# Circuito_part1_Altium.net
KiCad netlist of a schematic drawn in Altium Designer
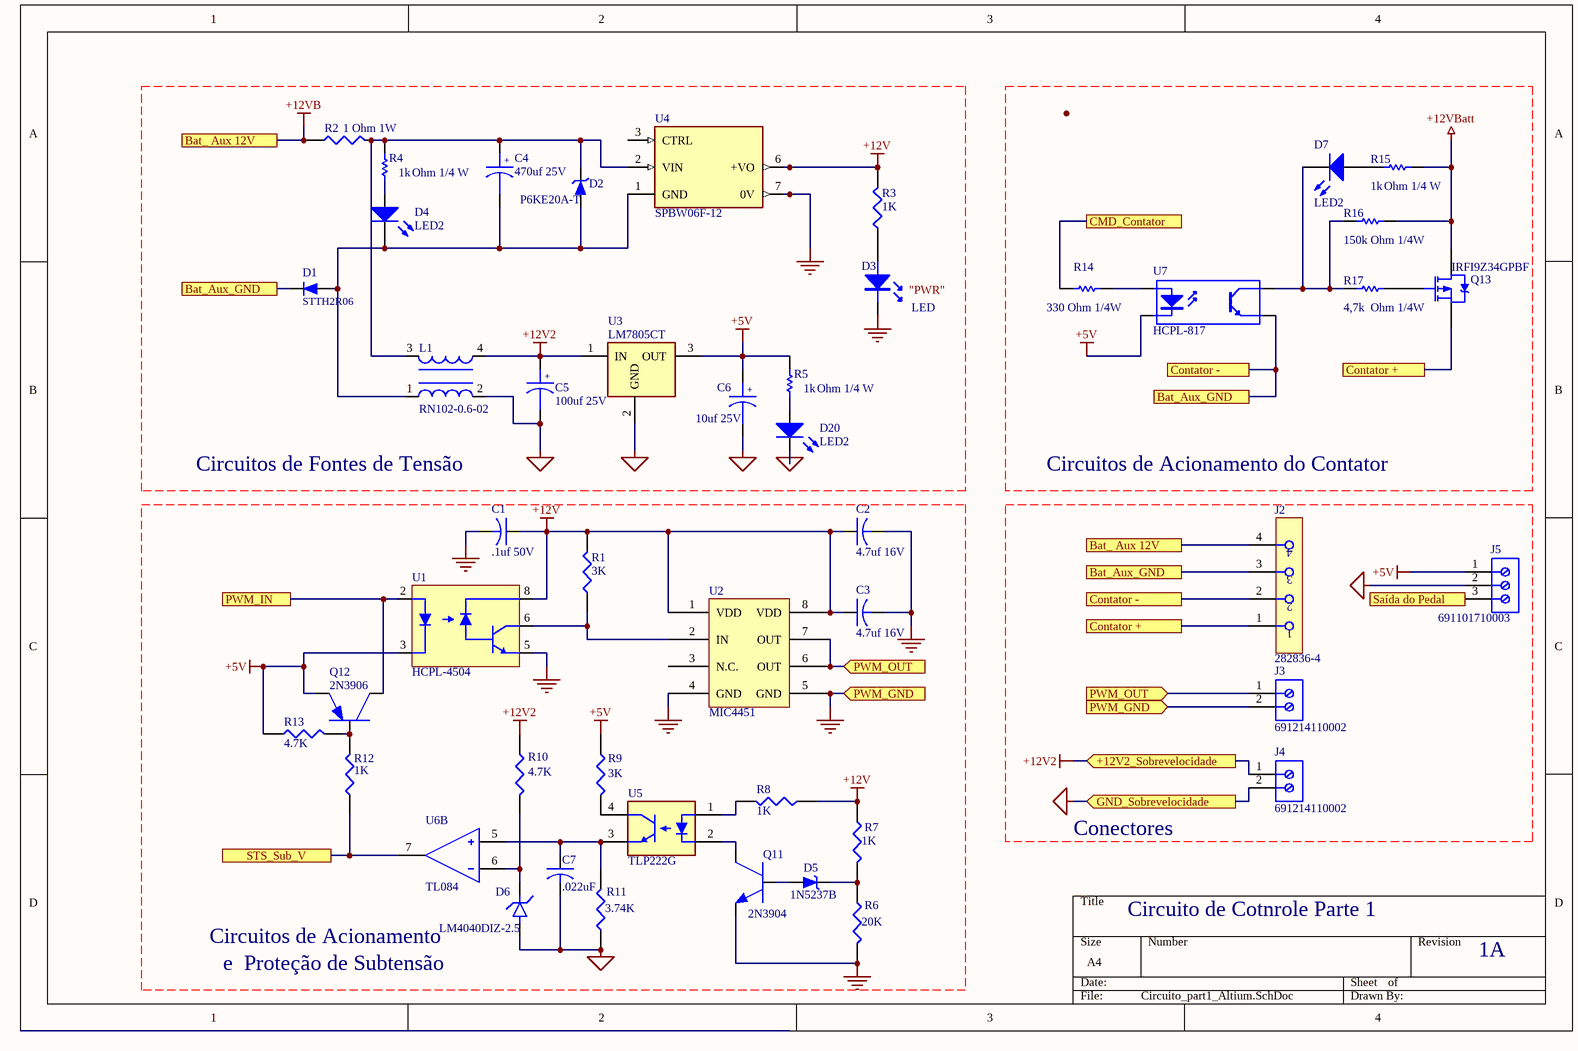
[diagram p0: Circuito_part1_Altium.SchDoc]

(export (version "E")
  (design (tool "Eeschema 10.0.6"))
  (components
    (comp (ref "C1")
      (value ".1uf 50V")
      (footprint "RAD0.2")
      (description "Capacitor")
      (libsource (lib "*") (part "CAPACITOR"))
    )
    (comp (ref "C2")
      (value "4.7uf 16V")
      (footprint "RAD0.2")
      (description "Capacitor")
      (libsource (lib "*") (part "CAPACITOR"))
    )
    (comp (ref "C3")
      (value "4.7uf 16V")
      (footprint "RAD0.2")
      (description "Capacitor")
      (libsource (lib "*") (part "CAPACITOR"))
    )
    (comp (ref "C4")
      (value "470uf 25V")
      (footprint "FC/10/5/0.6")
      (description "Capacitor")
      (libsource (lib "*") (part "CAPACITOR POL"))
    )
    (comp (ref "C5")
      (value "100uf 25V")
      (footprint "RB.1/.25")
      (description "Capacitor")
      (libsource (lib "*") (part "CAPACITOR POL"))
    )
    (comp (ref "C6")
      (value "10uf 25V")
      (footprint "RB.079/.2")
      (description "Capacitor")
      (libsource (lib "*") (part "CAPACITOR POL"))
    )
    (comp (ref "C7")
      (value ".022uF")
      (footprint "RAD0.2")
      (description "Capacitor")
      (libsource (lib "*") (part "CAPACITOR"))
    )
    (comp (ref "D1")
      (value "STTH2R06")
      (footprint "DIODE/AXIAL/11/3/0.9")
      (libsource (lib "*") (part "MYDIODE"))
    )
    (comp (ref "D2")
      (value "P6KE20A-T")
      (footprint "DIODE/AXIAL/11/3/0.9")
      (libsource (lib "*") (part "TRANSZORB-UNIDIRECTIONAL"))
    )
    (comp (ref "D3") (value "LED") (footprint "LUMEX SSL-LX5093") (libsource (lib "*") (part "MYLED")))
    (comp (ref "D4")
      (value "LED2")
      (footprint "3.2X1.6X1.1")
      (description "+12 V")
      (fields (field (name "PUBLISHER") "Altium Limited"))
      (libsource (lib "Miscellaneous Devices") (part "LED2"))
    )
    (comp (ref "D5") (value "1N5237B") (footprint "DIODE0.3") (libsource (lib "*") (part "MYZENER")))
    (comp (ref "D6")
      (value "LM4040DIZ-2.5")
      (footprint "TO-92C1")
      (libsource (lib "*") (part "LM4040DIZ-2.5"))
    )
    (comp (ref "D7")
      (value "LED2")
      (footprint "3.2X1.6X1.1")
      (description "+5 V")
      (fields (field (name "PUBLISHER") "Altium Limited"))
      (libsource (lib "Miscellaneous Devices") (part "LED2"))
    )
    (comp (ref "D20")
      (value "LED2")
      (footprint "3.2X1.6X1.1")
      (description "+5 V")
      (fields (field (name "PUBLISHER") "Altium Limited"))
      (libsource (lib "Miscellaneous Devices") (part "LED2"))
    )
    (comp (ref "J2")
      (value "282836-4")
      (footprint "FP-282836-4-MFG")
      (description "282836-4 Connector, Terminal Block; Wire Receptacle; 4 Pos.; 16-30 AWG; 0.197 in. CL; Sid")
      (fields (field (name "VOLTAGE") "300V"))
      (libsource (lib "Altium Content Vault") (part "282836-4"))
    )
    (comp (ref "J3")
      (value "691214110002")
      (footprint "691214110002")
      (fields (field (name "VOLTAGE") "300V"))
      (libsource (lib "Altium Content Vault") (part "TBL - 1R - 02P - Screw"))
    )
    (comp (ref "J4")
      (value "691214110002")
      (footprint "691214110002")
      (fields (field (name "VOLTAGE") "300V"))
      (libsource (lib "Altium Content Vault") (part "TBL - 1R - 02P - Screw"))
    )
    (comp (ref "J5")
      (value "691101710003")
      (footprint "691101710003")
      (fields (field (name "VOLTAGE") "250V"))
      (libsource (lib "Altium Content Vault") (part "TBL - 1R - 03P - Screw"))
    )
    (comp (ref "L1")
      (value "RN102-0.6-02")
      (footprint "RN102")
      (description "Common-Mode Choke")
      (libsource (lib "*") (part "RN102-0.6-02"))
    )
    (comp (ref "Q11") (value "2N3904") (footprint "TO-92MY1") (libsource (lib "*") (part "NPN")))
    (comp (ref "Q12") (value "2N3906") (footprint "TO-92MY1") (libsource (lib "*") (part "PNP")))
    (comp (ref "Q13")
      (value "IRFI9Z34GPBF")
      (footprint "TO-220AB")
      (description "P-Channel Power MOSFET")
      (fields (field (name "PUBLISHER") "Altium Limited"))
      (libsource (lib "Miscellaneous Devices") (part "PMOS-2"))
    )
    (comp (ref "R1") (value "3K") (footprint "AXIAL0.4") (libsource (lib "*") (part "RES1")))
    (comp (ref "R2") (value "1 Ohm 1W") (footprint "AXIAL0.7") (libsource (lib "*") (part "RES1")))
    (comp (ref "R3") (value "1K") (footprint "AXIAL0.4") (libsource (lib "*") (part "RES1")))
    (comp (ref "R4")
      (value "Ohm 1/4 W")
      (footprint "AXIAL-0.3")
      (description "Resistor")
      (fields (field (name "ALTIUM_VALUE") "1k") (field (name "PUBLISHER") "Altium Limited"))
      (libsource (lib "Miscellaneous Devices") (part "Res1"))
    )
    (comp (ref "R5")
      (value "Ohm 1/4 W")
      (footprint "AXIAL-0.3")
      (description "Resistor")
      (fields (field (name "ALTIUM_VALUE") "1k") (field (name "PUBLISHER") "Altium Limited"))
      (libsource (lib "Miscellaneous Devices") (part "Res1"))
    )
    (comp (ref "R6") (value "20K") (footprint "AXIAL0.4") (libsource (lib "*") (part "RES1")))
    (comp (ref "R7") (value "1K") (footprint "AXIAL0.4") (libsource (lib "*") (part "RES1")))
    (comp (ref "R8") (value "1K") (footprint "AXIAL0.4") (libsource (lib "*") (part "RES1")))
    (comp (ref "R9") (value "3K") (footprint "AXIAL0.4") (libsource (lib "*") (part "RES1")))
    (comp (ref "R10") (value "4.7K") (footprint "AXIAL0.4") (libsource (lib "*") (part "RES1")))
    (comp (ref "R11") (value "3.74K") (footprint "AXIAL0.4") (libsource (lib "*") (part "RES1")))
    (comp (ref "R12") (value "1K") (footprint "AXIAL0.4") (libsource (lib "*") (part "RES1")))
    (comp (ref "R13") (value "4.7K") (footprint "AXIAL0.4") (libsource (lib "*") (part "RES1")))
    (comp (ref "R14")
      (value "330 Ohm 1/4W")
      (footprint "AXIAL-0.3")
      (description "Resistor")
      (fields (field (name "PUBLISHER") "Altium Limited"))
      (libsource (lib "Miscellaneous Devices") (part "Res1"))
    )
    (comp (ref "R15")
      (value "Ohm 1/4 W")
      (footprint "AXIAL-0.3")
      (description "Resistor")
      (fields (field (name "ALTIUM_VALUE") "1k") (field (name "PUBLISHER") "Altium Limited"))
      (libsource (lib "Miscellaneous Devices") (part "Res1"))
    )
    (comp (ref "R16")
      (value "Ohm 1/4W")
      (footprint "AXIAL-0.3")
      (description "Resistor")
      (fields (field (name "ALTIUM_VALUE") "150k") (field (name "PUBLISHER") "Altium Limited"))
      (libsource (lib "Miscellaneous Devices") (part "Res1"))
    )
    (comp (ref "R17")
      (value "Ohm 1/4W")
      (footprint "AXIAL-0.3")
      (description "Resistor")
      (fields (field (name "ALTIUM_VALUE") "4,7k") (field (name "PUBLISHER") "Altium Limited"))
      (libsource (lib "Miscellaneous Devices") (part "Res1"))
    )
    (comp (ref "U1")
      (value "HCPL-4504")
      (footprint "DIP8")
      (description "Optocoupler with high CMRR")
      (libsource (lib "*") (part "HCPL-4504"))
    )
    (comp (ref "U2")
      (value "MIC4451")
      (footprint "DIP8")
      (description "FET Driver, 9A")
      (libsource (lib "*") (part "MIC4451"))
    )
    (comp (ref "U3")
      (value "LM7805CT")
      (footprint "TO-220-PAR-HS-MOUNT")
      (libsource (lib "*") (part "LM7805CT"))
    )
    (comp (ref "U4")
      (value "SPBW06F-12")
      (footprint "CONV_PQQ6W-Q24-S12-S")
      (description "DC-DC CONVERTER")
      (fields (field (name "MF") "{'manufacturer': u'CUI'}") (field (name "MP") "PQQ6W-Q24-S12-S"))
      (libsource (lib "PQQ6W-Q24-S12-S") (part "PQQ6W-Q24-S12-S"))
    )
    (comp (ref "U5") (value "TLP222G") (footprint "DIP4") (libsource (lib "*") (part "PS2501-1")))
    (comp (ref "U6") (value "TL084") (footprint "DIP8") (libsource (lib "*") (part "LM393M")))
    (comp (ref "U7")
      (value "HCPL-817")
      (footprint "DIP-4")
      (description "4-Pin Phototransistor Optocoupler")
      (fields (field (name "PUBLISHER") "Altium Limited"))
      (libsource (lib "Miscellaneous Devices") (part "Optoisolator1"))
    )
  )
  (nets
    (net (code "1") (name "+5V") (class "Default")
      (node (ref "C6") (pin "1") (pinfunction "1_1") (pintype "passive"))
      (node (ref "J5") (pin "1") (pinfunction "1_1") (pintype "passive"))
      (node (ref "Q12") (pin "2") (pinfunction "E_2") (pintype "passive"))
      (node (ref "R13") (pin "1") (pinfunction "1_1") (pintype "passive"))
      (node (ref "R5") (pin "1") (pinfunction "1_1") (pintype "passive"))
      (node (ref "R9") (pin "1") (pinfunction "1_1") (pintype "passive"))
      (node (ref "U1") (pin "3") (pinfunction "K_3") (pintype "passive"))
      (node (ref "U3") (pin "3") (pinfunction "OUT_3") (pintype "passive"))
      (node (ref "U7") (pin "2") (pinfunction "K_2") (pintype "passive"))
    )
    (net (code "2") (name "+12V") (class "Default")
      (node (ref "C1") (pin "1") (pinfunction "1_1") (pintype "passive"))
      (node (ref "C2") (pin "1") (pinfunction "1_1") (pintype "passive"))
      (node (ref "C3") (pin "1") (pinfunction "1_1") (pintype "passive"))
      (node (ref "R1") (pin "2") (pinfunction "2_2") (pintype "passive"))
      (node (ref "R3") (pin "2") (pinfunction "2_2") (pintype "passive"))
      (node (ref "R7") (pin "1") (pinfunction "1_1") (pintype "passive"))
      (node (ref "R8") (pin "1") (pinfunction "1_1") (pintype "passive"))
      (node (ref "U1") (pin "8") (pinfunction "VCC_8") (pintype "passive"))
      (node (ref "U2") (pin "1") (pinfunction "VDD_1") (pintype "passive"))
      (node (ref "U2") (pin "8") (pinfunction "VDD_8") (pintype "passive"))
      (node (ref "U4") (pin "6") (pinfunction "+VO_6") (pintype "output"))
    )
    (net (code "3") (name "+12V2") (class "Default")
      (node (ref "C5") (pin "1") (pinfunction "1_1") (pintype "passive"))
      (node (ref "J4") (pin "1") (pinfunction "1_1") (pintype "passive"))
      (node (ref "L1") (pin "4") (pinfunction "4_4") (pintype "passive"))
      (node (ref "R10") (pin "1") (pinfunction "1_1") (pintype "passive"))
      (node (ref "U3") (pin "1") (pinfunction "IN_1") (pintype "passive"))
    )
    (net (code "4") (name "+12VB") (class "Default")
      (node (ref "J2") (pin "4") (pinfunction "4_4") (pintype "passive"))
      (node (ref "R2") (pin "1") (pinfunction "1_1") (pintype "passive"))
    )
    (net (code "5") (name "+12VBatt") (class "Default")
      (node (ref "Q13") (pin "2") (pinfunction "D_2") (pintype "passive"))
      (node (ref "R15") (pin "1") (pinfunction "1_1") (pintype "passive"))
      (node (ref "R16") (pin "2") (pinfunction "2_2") (pintype "passive"))
    )
    (net (code "6") (name "/Bat_Aux_GND") (class "Default")
      (node (ref "D1") (pin "2") (pinfunction "K_2") (pintype "passive"))
      (node (ref "J2") (pin "2") (pinfunction "2_2") (pintype "passive"))
      (node (ref "J2") (pin "3") (pinfunction "3_3") (pintype "passive"))
      (node (ref "U7") (pin "3") (pinfunction "E_3") (pintype "passive"))
    )
    (net (code "7") (name "/CMD_Contator") (class "Default")
      (node (ref "R14") (pin "1") (pinfunction "1_1") (pintype "passive"))
    )
    (net (code "8") (name "/Contator +") (class "Default")
      (node (ref "J2") (pin "1") (pinfunction "1_1") (pintype "passive"))
      (node (ref "Q13") (pin "3") (pinfunction "S_3") (pintype "passive"))
    )
    (net (code "9") (name "/PWM_IN") (class "Default")
      (node (ref "Q12") (pin "3") (pinfunction "C_3") (pintype "passive"))
      (node (ref "U1") (pin "2") (pinfunction "A_2") (pintype "passive"))
    )
    (net (code "10") (name "/PWM_OUT") (class "Default")
      (node (ref "J3") (pin "1") (pinfunction "1_1") (pintype "passive"))
      (node (ref "U2") (pin "6") (pinfunction "OUT_6") (pintype "passive"))
      (node (ref "U2") (pin "7") (pinfunction "OUT_7") (pintype "passive"))
    )
    (net (code "11") (name "/STS_Sub_V") (class "Default")
      (node (ref "R12") (pin "1") (pinfunction "1_1") (pintype "passive"))
      (node (ref "U6") (pin "7") (pinfunction "VOB_7") (pintype "passive"))
    )
    (net (code "12") (name "/Saída do Pedal") (class "Default")
      (node (ref "J5") (pin "3") (pinfunction "3_3") (pintype "passive"))
    )
    (net (code "13") (name "3") (class "Default")
      (node (ref "D6") (pin "1") (pinfunction "3_1") (pintype "passive"))
    )
    (net (code "14") (name "Net-(D1-A)") (class "Default")
      (node (ref "C4") (pin "2") (pinfunction "2_2") (pintype "passive"))
      (node (ref "D1") (pin "1") (pinfunction "A_1") (pintype "passive"))
      (node (ref "D2") (pin "1") (pinfunction "K_1") (pintype "passive"))
      (node (ref "D4") (pin "2") (pinfunction "K_2") (pintype "passive"))
      (node (ref "L1") (pin "1") (pinfunction "1_1") (pintype "passive"))
      (node (ref "U4") (pin "1") (pinfunction "GND_1") (pintype "power_in"))
    )
    (net (code "15") (name "Net-(D2-A)") (class "Default")
      (node (ref "C4") (pin "1") (pinfunction "1_1") (pintype "passive"))
      (node (ref "D2") (pin "2") (pinfunction "A_2") (pintype "passive"))
      (node (ref "L1") (pin "3") (pinfunction "3_3") (pintype "passive"))
      (node (ref "R2") (pin "2") (pinfunction "2_2") (pintype "passive"))
      (node (ref "R4") (pin "1") (pinfunction "1_1") (pintype "passive"))
      (node (ref "U4") (pin "2") (pinfunction "VIN_2") (pintype "input"))
    )
    (net (code "16") (name "Net-(D3-1)") (class "Default")
      (node (ref "D3") (pin "A") (pinfunction "1_A") (pintype "passive"))
      (node (ref "R3") (pin "1") (pinfunction "1_1") (pintype "passive"))
    )
    (net (code "17") (name "Net-(D4-A)") (class "Default")
      (node (ref "D4") (pin "1") (pinfunction "A_1") (pintype "passive"))
      (node (ref "R4") (pin "2") (pinfunction "2_2") (pintype "passive"))
    )
    (net (code "18") (name "Net-(D5-A)") (class "Default")
      (node (ref "D5") (pin "1") (pinfunction "A_1") (pintype "passive"))
      (node (ref "Q11") (pin "1") (pinfunction "B_1") (pintype "passive"))
    )
    (net (code "19") (name "Net-(D5-K)") (class "Default")
      (node (ref "D5") (pin "2") (pinfunction "K_2") (pintype "passive"))
      (node (ref "R6") (pin "1") (pinfunction "1_1") (pintype "passive"))
      (node (ref "R7") (pin "2") (pinfunction "2_2") (pintype "passive"))
    )
    (net (code "20") (name "Net-(D6-A)") (class "Default")
      (node (ref "D6") (pin "2") (pinfunction "A_2") (pintype "passive"))
      (node (ref "R10") (pin "2") (pinfunction "2_2") (pintype "passive"))
      (node (ref "U6") (pin "6") (pinfunction "INB-_6") (pintype "passive"))
    )
    (net (code "21") (name "Net-(D7-A)") (class "Default")
      (node (ref "D7") (pin "1") (pinfunction "A_1") (pintype "passive"))
      (node (ref "R15") (pin "2") (pinfunction "2_2") (pintype "passive"))
    )
    (net (code "22") (name "Net-(D7-K)") (class "Default")
      (node (ref "D7") (pin "2") (pinfunction "K_2") (pintype "passive"))
      (node (ref "R16") (pin "1") (pinfunction "1_1") (pintype "passive"))
      (node (ref "R17") (pin "1") (pinfunction "1_1") (pintype "passive"))
      (node (ref "U7") (pin "4") (pinfunction "C_4") (pintype "passive"))
    )
    (net (code "23") (name "Net-(D20-A)") (class "Default")
      (node (ref "D20") (pin "1") (pinfunction "A_1") (pintype "passive"))
      (node (ref "R5") (pin "2") (pinfunction "2_2") (pintype "passive"))
    )
    (net (code "24") (name "Net-(Q11-C)") (class "Default")
      (node (ref "Q11") (pin "3") (pinfunction "C_3") (pintype "passive"))
      (node (ref "U5") (pin "2") (pinfunction "K2_2") (pintype "passive"))
    )
    (net (code "25") (name "Net-(Q12-B)") (class "Default")
      (node (ref "Q12") (pin "1") (pinfunction "B_1") (pintype "passive"))
      (node (ref "R12") (pin "2") (pinfunction "2_2") (pintype "passive"))
      (node (ref "R13") (pin "2") (pinfunction "2_2") (pintype "passive"))
    )
    (net (code "26") (name "Net-(Q13-G)") (class "Default")
      (node (ref "Q13") (pin "1") (pinfunction "G_1") (pintype "passive"))
      (node (ref "R17") (pin "2") (pinfunction "2_2") (pintype "passive"))
    )
    (net (code "27") (name "Net-(U1-VO)") (class "Default")
      (node (ref "R1") (pin "1") (pinfunction "1_1") (pintype "passive"))
      (node (ref "U1") (pin "6") (pinfunction "VO_6") (pintype "passive"))
      (node (ref "U2") (pin "2") (pinfunction "IN_2") (pintype "passive"))
    )
    (net (code "28") (name "Net-(U5-A1)") (class "Default")
      (node (ref "R8") (pin "2") (pinfunction "2_2") (pintype "passive"))
      (node (ref "U5") (pin "1") (pinfunction "A1_1") (pintype "passive"))
    )
    (net (code "29") (name "Net-(U5-C1)") (class "Default")
      (node (ref "R9") (pin "2") (pinfunction "2_2") (pintype "passive"))
      (node (ref "U5") (pin "4") (pinfunction "C1_4") (pintype "passive"))
    )
    (net (code "30") (name "Net-(U5-E1)") (class "Default")
      (node (ref "C7") (pin "1") (pinfunction "1_1") (pintype "passive"))
      (node (ref "R11") (pin "2") (pinfunction "2_2") (pintype "passive"))
      (node (ref "U5") (pin "3") (pinfunction "E1_3") (pintype "passive"))
      (node (ref "U6") (pin "5") (pinfunction "INB+_5") (pintype "passive"))
    )
    (net (code "31") (name "Net-(U7-A)") (class "Default")
      (node (ref "R14") (pin "2") (pinfunction "2_2") (pintype "passive"))
      (node (ref "U7") (pin "1") (pinfunction "A_1") (pintype "passive"))
    )
    (net (code "32") (name "PGND") (class "Default")
      (node (ref "C1") (pin "2") (pinfunction "2_2") (pintype "passive"))
      (node (ref "C2") (pin "2") (pinfunction "2_2") (pintype "passive"))
      (node (ref "C3") (pin "2") (pinfunction "2_2") (pintype "passive"))
      (node (ref "D3") (pin "K") (pinfunction "2_K") (pintype "passive"))
      (node (ref "J3") (pin "2") (pinfunction "2_2") (pintype "passive"))
      (node (ref "Q11") (pin "2") (pinfunction "E_2") (pintype "passive"))
      (node (ref "R6") (pin "2") (pinfunction "2_2") (pintype "passive"))
      (node (ref "U1") (pin "5") (pinfunction "GND_5") (pintype "passive"))
      (node (ref "U2") (pin "4") (pinfunction "GND_4") (pintype "passive"))
      (node (ref "U2") (pin "5") (pinfunction "GND_5") (pintype "passive"))
      (node (ref "U4") (pin "7") (pinfunction "0V_7") (pintype "output"))
    )
    (net (code "33") (name "SGND") (class "Default")
      (node (ref "C5") (pin "2") (pinfunction "2_2") (pintype "passive"))
      (node (ref "C6") (pin "2") (pinfunction "2_2") (pintype "passive"))
      (node (ref "C7") (pin "2") (pinfunction "2_2") (pintype "passive"))
      (node (ref "D20") (pin "2") (pinfunction "K_2") (pintype "passive"))
      (node (ref "D6") (pin "3") (pinfunction "K_3") (pintype "passive"))
      (node (ref "J4") (pin "2") (pinfunction "2_2") (pintype "passive"))
      (node (ref "J5") (pin "2") (pinfunction "2_2") (pintype "passive"))
      (node (ref "L1") (pin "2") (pinfunction "2_2") (pintype "passive"))
      (node (ref "R11") (pin "1") (pinfunction "1_1") (pintype "passive"))
      (node (ref "U3") (pin "2") (pinfunction "GND_2") (pintype "passive"))
    )
    (net (code "34") (name "unconnected-(U2-N.C.-Pad3)") (class "Default")
      (node (ref "U2") (pin "3") (pinfunction "N.C._3") (pintype "passive"))
    )
    (net (code "35") (name "unconnected-(U4-CTRL-Pad3)") (class "Default")
      (node (ref "U4") (pin "3") (pinfunction "CTRL_3") (pintype "input"))
    )
  )
)
